# nomis-memory-game-v01.net
KiCad netlist of a schematic drawn in EAGLE
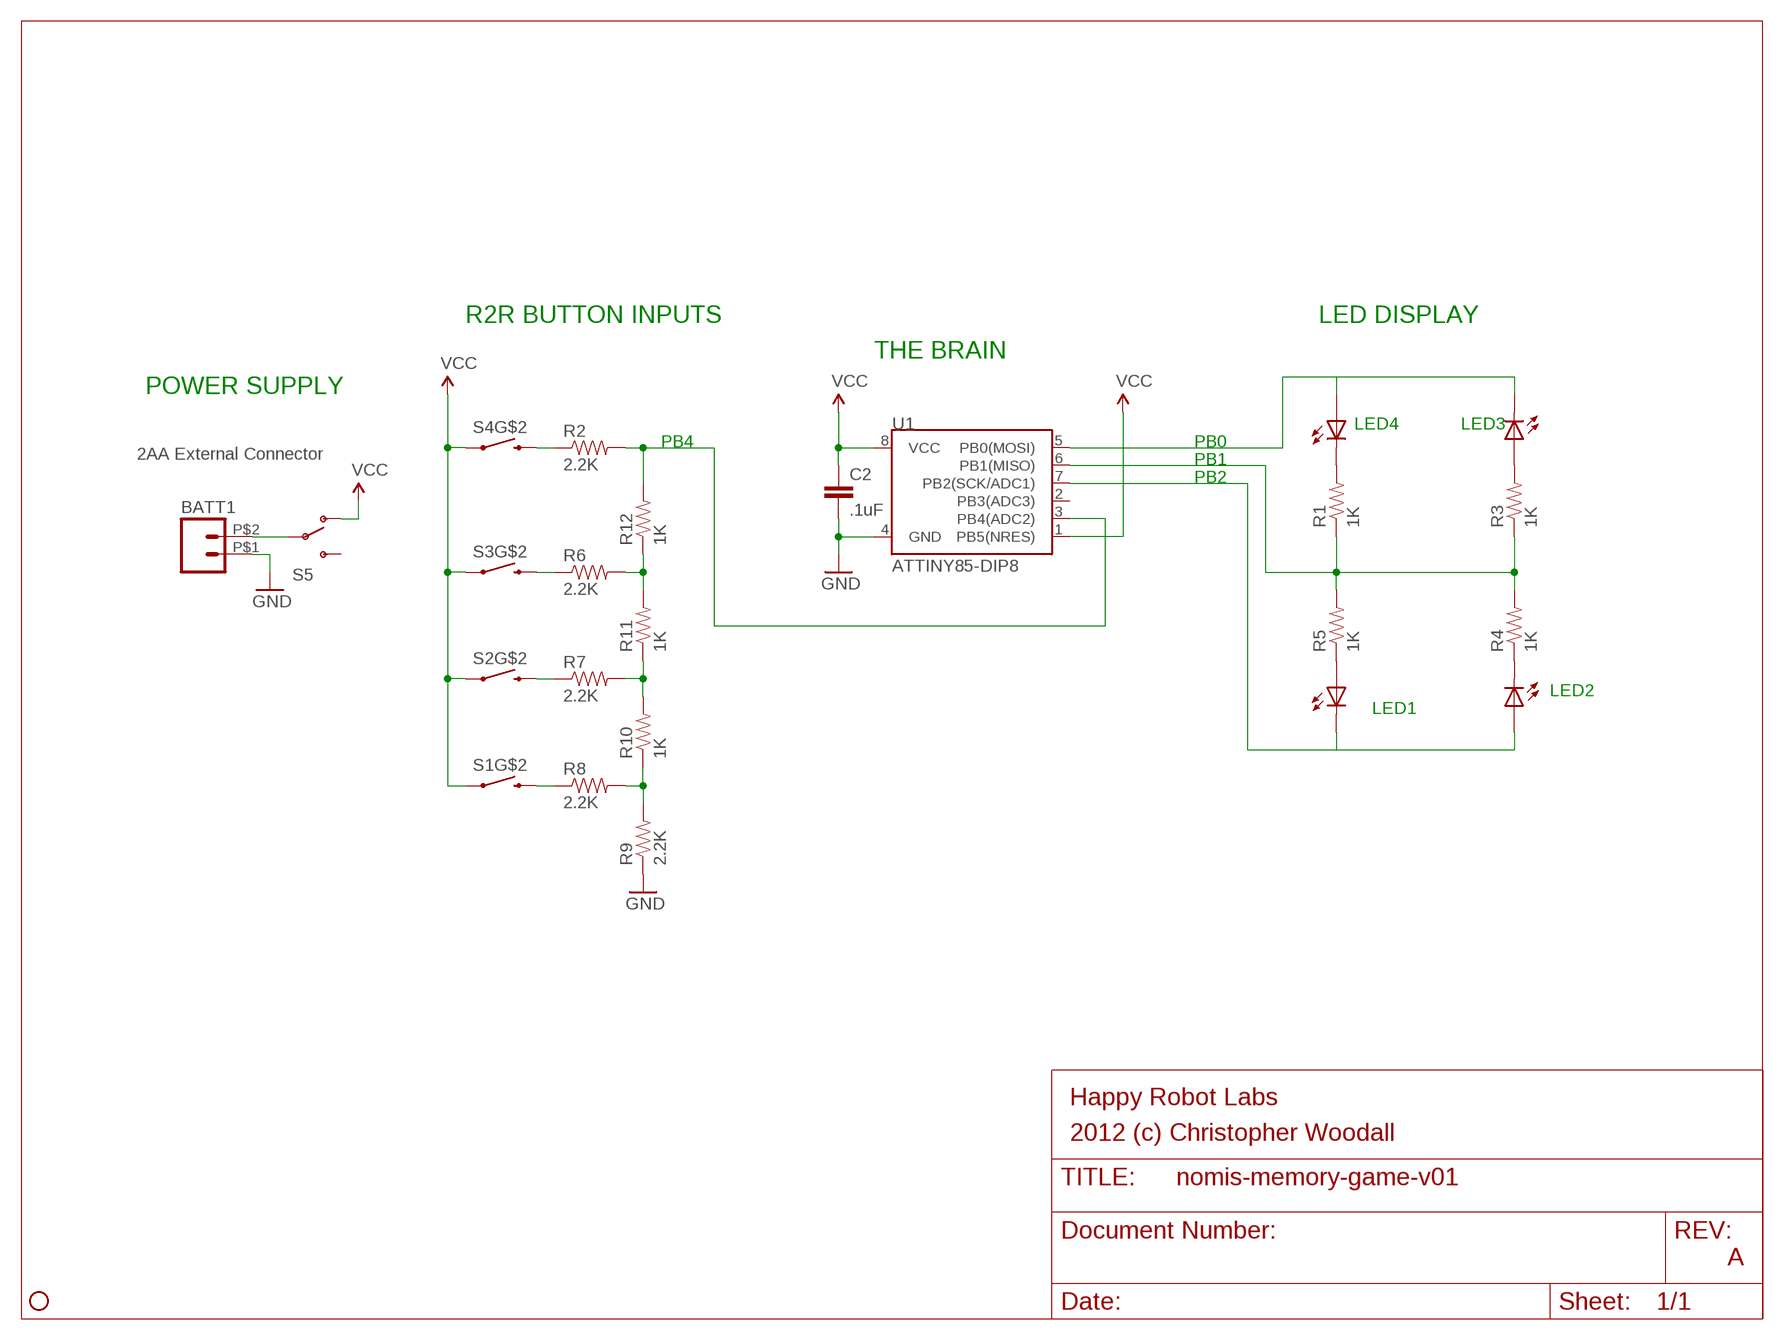
[diagram p0: schematic, sheet 1]

(export (version "E")
  (design (tool "Eeschema 10.0.6"))
  (components
    (comp (ref "BATT1")
      (value "2AA External Connector")
      (footprint "eagle-import:1X02_BIG")
      (libsource (lib "eagle-import") (part "M02PTH2"))
    )
    (comp (ref "C2")
      (value ".1uF")
      (footprint "eagle-import:CAP-PTH-SMALL")
      (libsource (lib "eagle-import") (part "CAPPTH"))
    )
    (comp (ref "JP1")
      (value "STAND-OFFTIGHT")
      (footprint "eagle-import:STAND-OFF-TIGHT")
      (libsource (lib "eagle-import") (part "STAND-OFFTIGHT"))
    )
    (comp (ref "JP2")
      (value "STAND-OFFTIGHT")
      (footprint "eagle-import:STAND-OFF-TIGHT")
      (libsource (lib "eagle-import") (part "STAND-OFFTIGHT"))
    )
    (comp (ref "JP3")
      (value "STAND-OFFTIGHT")
      (footprint "eagle-import:STAND-OFF-TIGHT")
      (libsource (lib "eagle-import") (part "STAND-OFFTIGHT"))
    )
    (comp (ref "JP4")
      (value "STAND-OFFTIGHT")
      (footprint "eagle-import:STAND-OFF-TIGHT")
      (libsource (lib "eagle-import") (part "STAND-OFFTIGHT"))
    )
    (comp (ref "R1")
      (value "1K")
      (footprint "eagle-import:AXIAL-0.4")
      (libsource (lib "eagle-import") (part "RESISTORPTH-1/4W"))
    )
    (comp (ref "R2")
      (value "2.2K")
      (footprint "eagle-import:AXIAL-0.4")
      (libsource (lib "eagle-import") (part "RESISTORPTH-1/4W"))
    )
    (comp (ref "R3")
      (value "1K")
      (footprint "eagle-import:AXIAL-0.4")
      (libsource (lib "eagle-import") (part "RESISTORPTH-1/4W"))
    )
    (comp (ref "R4")
      (value "1K")
      (footprint "eagle-import:AXIAL-0.4")
      (libsource (lib "eagle-import") (part "RESISTORPTH-1/4W"))
    )
    (comp (ref "R5")
      (value "1K")
      (footprint "eagle-import:AXIAL-0.4")
      (libsource (lib "eagle-import") (part "RESISTORPTH-1/4W"))
    )
    (comp (ref "R6")
      (value "2.2K")
      (footprint "eagle-import:AXIAL-0.4")
      (libsource (lib "eagle-import") (part "RESISTORPTH-1/4W"))
    )
    (comp (ref "R7")
      (value "2.2K")
      (footprint "eagle-import:AXIAL-0.4")
      (libsource (lib "eagle-import") (part "RESISTORPTH-1/4W"))
    )
    (comp (ref "R8")
      (value "2.2K")
      (footprint "eagle-import:AXIAL-0.4")
      (libsource (lib "eagle-import") (part "RESISTORPTH-1/4W"))
    )
    (comp (ref "R9")
      (value "2.2K")
      (footprint "eagle-import:AXIAL-0.4")
      (libsource (lib "eagle-import") (part "RESISTORPTH-1/4W"))
    )
    (comp (ref "R10")
      (value "1K")
      (footprint "eagle-import:AXIAL-0.4")
      (libsource (lib "eagle-import") (part "RESISTORPTH-1/4W"))
    )
    (comp (ref "R11")
      (value "1K")
      (footprint "eagle-import:AXIAL-0.4")
      (libsource (lib "eagle-import") (part "RESISTORPTH-1/4W"))
    )
    (comp (ref "R12")
      (value "1K")
      (footprint "eagle-import:AXIAL-0.4")
      (libsource (lib "eagle-import") (part "RESISTORPTH-1/4W"))
    )
    (comp (ref "S1")
      (value "SWITCH-MOMENTARY-LED-SPLIT")
      (footprint "eagle-import:TACTILE-PTH-LED-12MM")
      (libsource (lib "eagle-import") (part "SWITCH-MOMENTARY-LED-SPLIT"))
    )
    (comp (ref "S2")
      (value "SWITCH-MOMENTARY-LED-SPLIT")
      (footprint "eagle-import:TACTILE-PTH-LED-12MM")
      (libsource (lib "eagle-import") (part "SWITCH-MOMENTARY-LED-SPLIT"))
    )
    (comp (ref "S3")
      (value "SWITCH-MOMENTARY-LED-SPLIT")
      (footprint "eagle-import:TACTILE-PTH-LED-12MM")
      (libsource (lib "eagle-import") (part "SWITCH-MOMENTARY-LED-SPLIT"))
    )
    (comp (ref "S4")
      (value "SWITCH-MOMENTARY-LED-SPLIT")
      (footprint "eagle-import:TACTILE-PTH-LED-12MM")
      (libsource (lib "eagle-import") (part "SWITCH-MOMENTARY-LED-SPLIT"))
    )
    (comp (ref "S5")
      (value "SWITCH-SPSTPTH")
      (footprint "eagle-import:SWITCH-SPDT")
      (libsource (lib "eagle-import") (part "SWITCH-SPSTPTH"))
    )
    (comp (ref "U1")
      (value "ATTINY85-DIP8")
      (footprint "eagle-import:DIP08")
      (libsource (lib "eagle-import") (part "ATTINY45DIP8"))
    )
  )
  (nets
    (net (code "1") (name "GND") (class "Default")
      (node (ref "BATT1") (pin "P$1") (pinfunction "1_P$1") (pintype "passive"))
      (node (ref "C2") (pin "2") (pinfunction "2_2") (pintype "passive"))
      (node (ref "R9") (pin "P$1") (pinfunction "1_P$1") (pintype "passive"))
      (node (ref "U1") (pin "4") (pinfunction "GND_4") (pintype "bidirectional"))
    )
    (net (code "2") (name "Net-(BATT1-2)") (class "Default")
      (node (ref "BATT1") (pin "P$2") (pinfunction "2_P$2") (pintype "passive"))
      (node (ref "S5") (pin "2") (pinfunction "P_2") (pintype "passive"))
    )
    (net (code "3") (name "Net-(R1-1)") (class "Default")
      (node (ref "R1") (pin "P$1") (pinfunction "1_P$1") (pintype "passive"))
      (node (ref "R3") (pin "P$1") (pinfunction "1_P$1") (pintype "passive"))
      (node (ref "R4") (pin "P$2") (pinfunction "2_P$2") (pintype "passive"))
      (node (ref "R5") (pin "P$2") (pinfunction "2_P$2") (pintype "passive"))
      (node (ref "U1") (pin "6") (pinfunction "PB1(MISO)_6") (pintype "bidirectional"))
    )
    (net (code "4") (name "Net-(R1-2)") (class "Default")
      (node (ref "R1") (pin "P$2") (pinfunction "2_P$2") (pintype "passive"))
      (node (ref "S4") (pin "C") (pinfunction "C_C") (pintype "passive"))
    )
    (net (code "5") (name "Net-(R2-1)") (class "Default")
      (node (ref "R2") (pin "P$1") (pinfunction "1_P$1") (pintype "passive"))
      (node (ref "S4") (pin "3") (pinfunction "2_3") (pintype "passive"))
      (node (ref "S4") (pin "4") (pinfunction "2_4") (pintype "passive"))
    )
    (net (code "6") (name "Net-(R3-2)") (class "Default")
      (node (ref "R3") (pin "P$2") (pinfunction "2_P$2") (pintype "passive"))
      (node (ref "S3") (pin "A") (pinfunction "A_A") (pintype "passive"))
    )
    (net (code "7") (name "Net-(R4-1)") (class "Default")
      (node (ref "R4") (pin "P$1") (pinfunction "1_P$1") (pintype "passive"))
      (node (ref "S2") (pin "C") (pinfunction "C_C") (pintype "passive"))
    )
    (net (code "8") (name "Net-(R5-1)") (class "Default")
      (node (ref "R5") (pin "P$1") (pinfunction "1_P$1") (pintype "passive"))
      (node (ref "S1") (pin "A") (pinfunction "A_A") (pintype "passive"))
    )
    (net (code "9") (name "Net-(R6-1)") (class "Default")
      (node (ref "R6") (pin "P$1") (pinfunction "1_P$1") (pintype "passive"))
      (node (ref "S3") (pin "3") (pinfunction "2_3") (pintype "passive"))
      (node (ref "S3") (pin "4") (pinfunction "2_4") (pintype "passive"))
    )
    (net (code "10") (name "Net-(R7-1)") (class "Default")
      (node (ref "R7") (pin "P$1") (pinfunction "1_P$1") (pintype "passive"))
      (node (ref "S2") (pin "3") (pinfunction "2_3") (pintype "passive"))
      (node (ref "S2") (pin "4") (pinfunction "2_4") (pintype "passive"))
    )
    (net (code "11") (name "Net-(R8-1)") (class "Default")
      (node (ref "R8") (pin "P$1") (pinfunction "1_P$1") (pintype "passive"))
      (node (ref "S1") (pin "3") (pinfunction "2_3") (pintype "passive"))
      (node (ref "S1") (pin "4") (pinfunction "2_4") (pintype "passive"))
    )
    (net (code "12") (name "Net-(R10-1)") (class "Default")
      (node (ref "R10") (pin "P$1") (pinfunction "1_P$1") (pintype "passive"))
      (node (ref "R8") (pin "P$2") (pinfunction "2_P$2") (pintype "passive"))
      (node (ref "R9") (pin "P$2") (pinfunction "2_P$2") (pintype "passive"))
    )
    (net (code "13") (name "Net-(R10-2)") (class "Default")
      (node (ref "R10") (pin "P$2") (pinfunction "2_P$2") (pintype "passive"))
      (node (ref "R11") (pin "P$1") (pinfunction "1_P$1") (pintype "passive"))
      (node (ref "R7") (pin "P$2") (pinfunction "2_P$2") (pintype "passive"))
    )
    (net (code "14") (name "Net-(R11-2)") (class "Default")
      (node (ref "R11") (pin "P$2") (pinfunction "2_P$2") (pintype "passive"))
      (node (ref "R12") (pin "P$1") (pinfunction "1_P$1") (pintype "passive"))
      (node (ref "R6") (pin "P$2") (pinfunction "2_P$2") (pintype "passive"))
    )
    (net (code "15") (name "Net-(R12-2)") (class "Default")
      (node (ref "R12") (pin "P$2") (pinfunction "2_P$2") (pintype "passive"))
      (node (ref "R2") (pin "P$2") (pinfunction "2_P$2") (pintype "passive"))
      (node (ref "U1") (pin "3") (pinfunction "PB4(ADC2)_3") (pintype "bidirectional"))
    )
    (net (code "16") (name "Net-(U1-PB0(MOSI))") (class "Default")
      (node (ref "S3") (pin "C") (pinfunction "C_C") (pintype "passive"))
      (node (ref "S4") (pin "A") (pinfunction "A_A") (pintype "passive"))
      (node (ref "U1") (pin "5") (pinfunction "PB0(MOSI)_5") (pintype "bidirectional"))
    )
    (net (code "17") (name "Net-(U1-PB2(SCK{slash}ADC1))") (class "Default")
      (node (ref "S1") (pin "C") (pinfunction "C_C") (pintype "passive"))
      (node (ref "S2") (pin "A") (pinfunction "A_A") (pintype "passive"))
      (node (ref "U1") (pin "7") (pinfunction "PB2(SCK/ADC1)_7") (pintype "bidirectional"))
    )
    (net (code "18") (name "VCC") (class "Default")
      (node (ref "C2") (pin "1") (pinfunction "1_1") (pintype "passive"))
      (node (ref "S1") (pin "1") (pinfunction "1_1") (pintype "passive"))
      (node (ref "S1") (pin "2") (pinfunction "1_2") (pintype "passive"))
      (node (ref "S2") (pin "1") (pinfunction "1_1") (pintype "passive"))
      (node (ref "S2") (pin "2") (pinfunction "1_2") (pintype "passive"))
      (node (ref "S3") (pin "1") (pinfunction "1_1") (pintype "passive"))
      (node (ref "S3") (pin "2") (pinfunction "1_2") (pintype "passive"))
      (node (ref "S4") (pin "1") (pinfunction "1_1") (pintype "passive"))
      (node (ref "S4") (pin "2") (pinfunction "1_2") (pintype "passive"))
      (node (ref "S5") (pin "1") (pinfunction "O_1") (pintype "passive"))
      (node (ref "U1") (pin "1") (pinfunction "PB5(NRES)_1") (pintype "bidirectional"))
      (node (ref "U1") (pin "8") (pinfunction "VCC_8") (pintype "bidirectional"))
    )
    (net (code "19") (name "unconnected-(S5-S-Pad3)") (class "Default")
      (node (ref "S5") (pin "3") (pinfunction "S_3") (pintype "passive"))
    )
    (net (code "20") (name "unconnected-(U1-PB3(ADC3)-Pad2)") (class "Default")
      (node (ref "U1") (pin "2") (pinfunction "PB3(ADC3)_2") (pintype "bidirectional"))
    )
  )
)
